# OLDbattery_board.net
KiCad netlist of a schematic drawn in EAGLE
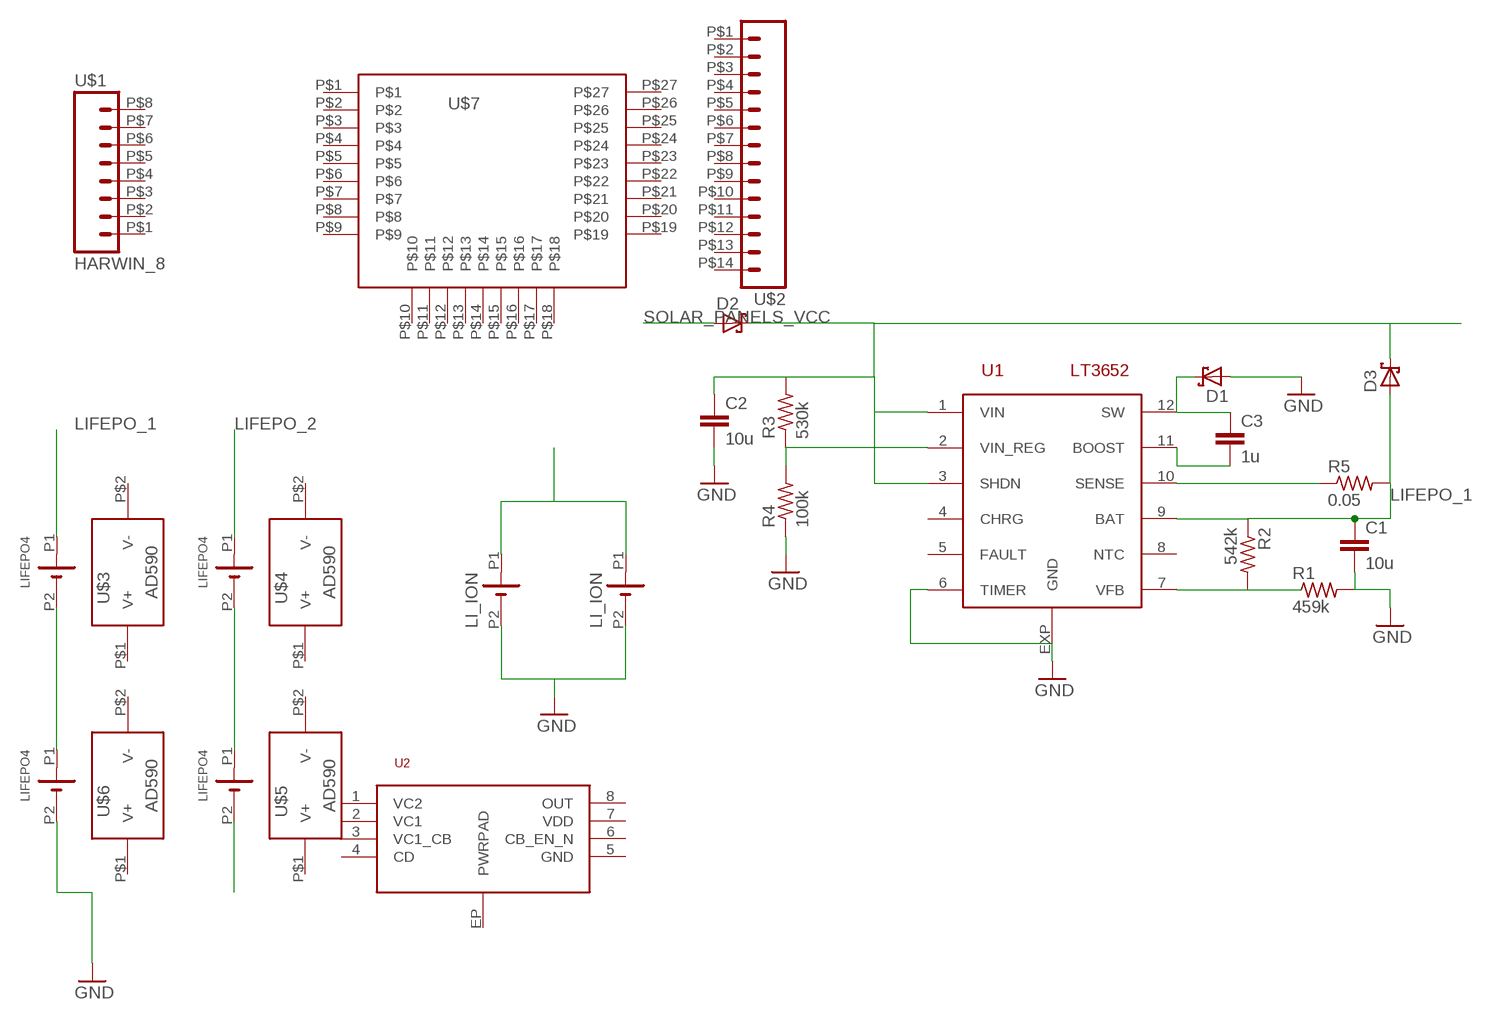
[diagram p0: schematic, sheet 1]

(export (version "E")
  (design (tool "Eeschema 10.0.6"))
  (components
    (comp (ref "C1")
      (value "10u")
      (footprint "eagle-import:C1210")
      (libsource (lib "eagle-import") (part "C-EUC1210"))
    )
    (comp (ref "C2")
      (value "10u")
      (footprint "eagle-import:C1210")
      (libsource (lib "eagle-import") (part "C-EUC1210"))
    )
    (comp (ref "C3")
      (value "1u")
      (footprint "eagle-import:C0805")
      (libsource (lib "eagle-import") (part "C-EUC0805"))
    )
    (comp (ref "D1")
      (value "SCHOTTKY-DIODE")
      (footprint "eagle-import:SOD123")
      (libsource (lib "eagle-import") (part "SCHOTTKY-DIODE"))
    )
    (comp (ref "D2")
      (value "SCHOTTKY-DIODE")
      (footprint "eagle-import:SOD123")
      (libsource (lib "eagle-import") (part "SCHOTTKY-DIODE"))
    )
    (comp (ref "D3")
      (value "SCHOTTKY-DIODE")
      (footprint "eagle-import:SOD123")
      (libsource (lib "eagle-import") (part "SCHOTTKY-DIODE"))
    )
    (comp (ref "LFP1")
      (value "LIFEPO4")
      (footprint "eagle-import:LIFEPO4")
      (libsource (lib "eagle-import") (part "LIFEPO4"))
    )
    (comp (ref "LFP2")
      (value "LIFEPO4")
      (footprint "eagle-import:LIFEPO4")
      (libsource (lib "eagle-import") (part "LIFEPO4"))
    )
    (comp (ref "LFP3")
      (value "LIFEPO4")
      (footprint "eagle-import:LIFEPO4")
      (libsource (lib "eagle-import") (part "LIFEPO4"))
    )
    (comp (ref "LFP4")
      (value "LIFEPO4")
      (footprint "eagle-import:LIFEPO4")
      (libsource (lib "eagle-import") (part "LIFEPO4"))
    )
    (comp (ref "R1")
      (value "459k")
      (footprint "eagle-import:R0805")
      (libsource (lib "eagle-import") (part "R-US_R0805"))
    )
    (comp (ref "R2")
      (value "542k")
      (footprint "eagle-import:R0805")
      (libsource (lib "eagle-import") (part "R-US_R0805"))
    )
    (comp (ref "R3")
      (value "530k")
      (footprint "eagle-import:R0805")
      (libsource (lib "eagle-import") (part "R-US_R0805"))
    )
    (comp (ref "R4")
      (value "100k")
      (footprint "eagle-import:R0805")
      (libsource (lib "eagle-import") (part "R-US_R0805"))
    )
    (comp (ref "R5")
      (value "0.05")
      (footprint "eagle-import:R0805")
      (libsource (lib "eagle-import") (part "R-US_R0805"))
    )
    (comp (ref "U$1")
      (value "HARWIN_8")
      (footprint "eagle-import:HARWIN_8")
      (libsource (lib "eagle-import") (part "HARWIN_8"))
    )
    (comp (ref "U$2")
      (value "HARWIN_14")
      (footprint "eagle-import:HARWIN_DATAMATE_14")
      (libsource (lib "eagle-import") (part "HARWIN_14"))
    )
    (comp (ref "U$3")
      (value "AD590-TH")
      (footprint "eagle-import:AD590TH")
      (libsource (lib "eagle-import") (part "AD590-TH"))
    )
    (comp (ref "U$4")
      (value "AD590-TH")
      (footprint "eagle-import:AD590TH")
      (libsource (lib "eagle-import") (part "AD590-TH"))
    )
    (comp (ref "U$5")
      (value "AD590-TH")
      (footprint "eagle-import:AD590TH")
      (libsource (lib "eagle-import") (part "AD590-TH"))
    )
    (comp (ref "U$6")
      (value "AD590-TH")
      (footprint "eagle-import:AD590TH")
      (libsource (lib "eagle-import") (part "AD590-TH"))
    )
    (comp (ref "U$7")
      (value "HARWIN_27")
      (footprint "eagle-import:HARWIN_DATAMATE_27")
      (libsource (lib "eagle-import") (part "HARWIN_27"))
    )
    (comp (ref "U$8")
      (value "LI_ION")
      (footprint "eagle-import:LI_ION")
      (libsource (lib "eagle-import") (part "LI_ION"))
    )
    (comp (ref "U$9")
      (value "LI_ION")
      (footprint "eagle-import:LI_ION")
      (libsource (lib "eagle-import") (part "LI_ION"))
    )
    (comp (ref "U1")
      (value "LT3652")
      (footprint "eagle-import:MSOP12")
      (libsource (lib "eagle-import") (part "LT3652"))
    )
    (comp (ref "U2")
      (value "BQ29209")
      (footprint "eagle-import:VSON8")
      (libsource (lib "eagle-import") (part "BQ29209"))
    )
  )
  (nets
    (net (code "1") (name "/LIFEPO_1") (class "Default")
      (node (ref "C1") (pin "1") (pinfunction "1_1") (pintype "passive"))
      (node (ref "D3") (pin "A") (pinfunction "A_A") (pintype "passive"))
      (node (ref "LFP1") (pin "P1") (pinfunction "+_P1") (pintype "passive"))
      (node (ref "R2") (pin "1") (pinfunction "1_1") (pintype "passive"))
      (node (ref "R5") (pin "2") (pinfunction "2_2") (pintype "passive"))
      (node (ref "U1") (pin "9") (pinfunction "BAT_9") (pintype "bidirectional"))
    )
    (net (code "2") (name "/LIFEPO_2") (class "Default")
      (node (ref "LFP2") (pin "P1") (pinfunction "+_P1") (pintype "passive"))
    )
    (net (code "3") (name "/SOLAR_PANELS_VCC") (class "Default")
      (node (ref "D2") (pin "A") (pinfunction "A_A") (pintype "passive"))
    )
    (net (code "4") (name "GND") (class "Default")
      (node (ref "C1") (pin "2") (pinfunction "2_2") (pintype "passive"))
      (node (ref "C2") (pin "2") (pinfunction "2_2") (pintype "passive"))
      (node (ref "D1") (pin "A") (pinfunction "A_A") (pintype "passive"))
      (node (ref "LFP3") (pin "P2") (pinfunction "-_P2") (pintype "passive"))
      (node (ref "R1") (pin "2") (pinfunction "2_2") (pintype "passive"))
      (node (ref "R4") (pin "1") (pinfunction "1_1") (pintype "passive"))
      (node (ref "U$8") (pin "P2") (pinfunction "-_P2") (pintype "passive"))
      (node (ref "U$9") (pin "P2") (pinfunction "-_P2") (pintype "passive"))
      (node (ref "U1") (pin "6") (pinfunction "TIMER_6") (pintype "bidirectional"))
      (node (ref "U1") (pin "EXP") (pinfunction "GND_EXP") (pintype "bidirectional"))
    )
    (net (code "5") (name "Net-(LFP1--)") (class "Default")
      (node (ref "LFP1") (pin "P2") (pinfunction "-_P2") (pintype "passive"))
      (node (ref "LFP3") (pin "P1") (pinfunction "+_P1") (pintype "passive"))
    )
    (net (code "6") (name "Net-(LFP2--)") (class "Default")
      (node (ref "LFP2") (pin "P2") (pinfunction "-_P2") (pintype "passive"))
      (node (ref "LFP4") (pin "P1") (pinfunction "+_P1") (pintype "passive"))
    )
    (net (code "7") (name "Net-(U$8-+)") (class "Default")
      (node (ref "U$8") (pin "P1") (pinfunction "+_P1") (pintype "passive"))
      (node (ref "U$9") (pin "P1") (pinfunction "+_P1") (pintype "passive"))
    )
    (net (code "8") (name "Net-(U1-BOOST)") (class "Default")
      (node (ref "C3") (pin "2") (pinfunction "2_2") (pintype "passive"))
      (node (ref "U1") (pin "11") (pinfunction "BOOST_11") (pintype "bidirectional"))
    )
    (net (code "9") (name "Net-(U1-SENSE)") (class "Default")
      (node (ref "R5") (pin "1") (pinfunction "1_1") (pintype "passive"))
      (node (ref "U1") (pin "10") (pinfunction "SENSE_10") (pintype "bidirectional"))
    )
    (net (code "10") (name "Net-(U1-SHDN)") (class "Default")
      (node (ref "C2") (pin "1") (pinfunction "1_1") (pintype "passive"))
      (node (ref "D2") (pin "C") (pinfunction "C_C") (pintype "passive"))
      (node (ref "D3") (pin "C") (pinfunction "C_C") (pintype "passive"))
      (node (ref "R3") (pin "2") (pinfunction "2_2") (pintype "passive"))
      (node (ref "U1") (pin "1") (pinfunction "VIN_1") (pintype "bidirectional"))
      (node (ref "U1") (pin "3") (pinfunction "SHDN_3") (pintype "bidirectional"))
    )
    (net (code "11") (name "Net-(U1-SW)") (class "Default")
      (node (ref "C3") (pin "1") (pinfunction "1_1") (pintype "passive"))
      (node (ref "D1") (pin "C") (pinfunction "C_C") (pintype "passive"))
      (node (ref "U1") (pin "12") (pinfunction "SW_12") (pintype "bidirectional"))
    )
    (net (code "12") (name "Net-(U1-VFB)") (class "Default")
      (node (ref "R2") (pin "2") (pinfunction "2_2") (pintype "passive"))
      (node (ref "U1") (pin "7") (pinfunction "VFB_7") (pintype "bidirectional"))
    )
    (net (code "13") (name "Net-(U1-VIN_REG)") (class "Default")
      (node (ref "R3") (pin "1") (pinfunction "1_1") (pintype "passive"))
      (node (ref "R4") (pin "2") (pinfunction "2_2") (pintype "passive"))
      (node (ref "U1") (pin "2") (pinfunction "VIN_REG_2") (pintype "bidirectional"))
    )
    (net (code "14") (name "unconnected-(LFP4---PadP2)") (class "Default")
      (node (ref "LFP4") (pin "P2") (pinfunction "-_P2") (pintype "passive"))
    )
    (net (code "15") (name "unconnected-(R1-Pad1)") (class "Default")
      (node (ref "R1") (pin "1") (pinfunction "1_1") (pintype "passive"))
    )
    (net (code "16") (name "unconnected-(U$1-1-PadP$1)") (class "Default")
      (node (ref "U$1") (pin "P$1") (pinfunction "1_P$1") (pintype "passive"))
    )
    (net (code "17") (name "unconnected-(U$1-2-PadP$2)") (class "Default")
      (node (ref "U$1") (pin "P$2") (pinfunction "2_P$2") (pintype "passive"))
    )
    (net (code "18") (name "unconnected-(U$1-3-PadP$3)") (class "Default")
      (node (ref "U$1") (pin "P$3") (pinfunction "3_P$3") (pintype "passive"))
    )
    (net (code "19") (name "unconnected-(U$1-4-PadP$4)") (class "Default")
      (node (ref "U$1") (pin "P$4") (pinfunction "4_P$4") (pintype "passive"))
    )
    (net (code "20") (name "unconnected-(U$1-5-PadP$5)") (class "Default")
      (node (ref "U$1") (pin "P$5") (pinfunction "5_P$5") (pintype "passive"))
    )
    (net (code "21") (name "unconnected-(U$1-6-PadP$6)") (class "Default")
      (node (ref "U$1") (pin "P$6") (pinfunction "6_P$6") (pintype "passive"))
    )
    (net (code "22") (name "unconnected-(U$1-7-PadP$7)") (class "Default")
      (node (ref "U$1") (pin "P$7") (pinfunction "7_P$7") (pintype "passive"))
    )
    (net (code "23") (name "unconnected-(U$1-8-PadP$8)") (class "Default")
      (node (ref "U$1") (pin "P$8") (pinfunction "8_P$8") (pintype "passive"))
    )
    (net (code "24") (name "unconnected-(U$2-1-PadP$1)") (class "Default")
      (node (ref "U$2") (pin "P$1") (pinfunction "1_P$1") (pintype "passive"))
    )
    (net (code "25") (name "unconnected-(U$2-2-PadP$2)") (class "Default")
      (node (ref "U$2") (pin "P$2") (pinfunction "2_P$2") (pintype "passive"))
    )
    (net (code "26") (name "unconnected-(U$2-3-PadP$3)") (class "Default")
      (node (ref "U$2") (pin "P$3") (pinfunction "3_P$3") (pintype "passive"))
    )
    (net (code "27") (name "unconnected-(U$2-4-PadP$4)") (class "Default")
      (node (ref "U$2") (pin "P$4") (pinfunction "4_P$4") (pintype "passive"))
    )
    (net (code "28") (name "unconnected-(U$2-5-PadP$5)") (class "Default")
      (node (ref "U$2") (pin "P$5") (pinfunction "5_P$5") (pintype "passive"))
    )
    (net (code "29") (name "unconnected-(U$2-6-PadP$6)") (class "Default")
      (node (ref "U$2") (pin "P$6") (pinfunction "6_P$6") (pintype "passive"))
    )
    (net (code "30") (name "unconnected-(U$2-7-PadP$7)") (class "Default")
      (node (ref "U$2") (pin "P$7") (pinfunction "7_P$7") (pintype "passive"))
    )
    (net (code "31") (name "unconnected-(U$2-8-PadP$8)") (class "Default")
      (node (ref "U$2") (pin "P$8") (pinfunction "8_P$8") (pintype "passive"))
    )
    (net (code "32") (name "unconnected-(U$2-9-PadP$9)") (class "Default")
      (node (ref "U$2") (pin "P$9") (pinfunction "9_P$9") (pintype "passive"))
    )
    (net (code "33") (name "unconnected-(U$2-10-PadP$10)") (class "Default")
      (node (ref "U$2") (pin "P$10") (pinfunction "10_P$10") (pintype "passive"))
    )
    (net (code "34") (name "unconnected-(U$2-11-PadP$11)") (class "Default")
      (node (ref "U$2") (pin "P$11") (pinfunction "11_P$11") (pintype "passive"))
    )
    (net (code "35") (name "unconnected-(U$2-12-PadP$12)") (class "Default")
      (node (ref "U$2") (pin "P$12") (pinfunction "12_P$12") (pintype "passive"))
    )
    (net (code "36") (name "unconnected-(U$2-13-PadP$13)") (class "Default")
      (node (ref "U$2") (pin "P$13") (pinfunction "13_P$13") (pintype "passive"))
    )
    (net (code "37") (name "unconnected-(U$2-14-PadP$14)") (class "Default")
      (node (ref "U$2") (pin "P$14") (pinfunction "14_P$14") (pintype "passive"))
    )
    (net (code "38") (name "unconnected-(U$3-V+-PadP$1)") (class "Default")
      (node (ref "U$3") (pin "P$1") (pinfunction "V+_P$1") (pintype "bidirectional"))
    )
    (net (code "39") (name "unconnected-(U$3-V--PadP$2)") (class "Default")
      (node (ref "U$3") (pin "P$2") (pinfunction "V-_P$2") (pintype "bidirectional"))
    )
    (net (code "40") (name "unconnected-(U$4-V+-PadP$1)") (class "Default")
      (node (ref "U$4") (pin "P$1") (pinfunction "V+_P$1") (pintype "bidirectional"))
    )
    (net (code "41") (name "unconnected-(U$4-V--PadP$2)") (class "Default")
      (node (ref "U$4") (pin "P$2") (pinfunction "V-_P$2") (pintype "bidirectional"))
    )
    (net (code "42") (name "unconnected-(U$5-V+-PadP$1)") (class "Default")
      (node (ref "U$5") (pin "P$1") (pinfunction "V+_P$1") (pintype "bidirectional"))
    )
    (net (code "43") (name "unconnected-(U$5-V--PadP$2)") (class "Default")
      (node (ref "U$5") (pin "P$2") (pinfunction "V-_P$2") (pintype "bidirectional"))
    )
    (net (code "44") (name "unconnected-(U$6-V+-PadP$1)") (class "Default")
      (node (ref "U$6") (pin "P$1") (pinfunction "V+_P$1") (pintype "bidirectional"))
    )
    (net (code "45") (name "unconnected-(U$6-V--PadP$2)") (class "Default")
      (node (ref "U$6") (pin "P$2") (pinfunction "V-_P$2") (pintype "bidirectional"))
    )
    (net (code "46") (name "unconnected-(U$7-PadP$1)") (class "Default")
      (node (ref "U$7") (pin "P$1") (pinfunction "P$1_P$1") (pintype "bidirectional"))
    )
    (net (code "47") (name "unconnected-(U$7-PadP$2)") (class "Default")
      (node (ref "U$7") (pin "P$2") (pinfunction "P$2_P$2") (pintype "bidirectional"))
    )
    (net (code "48") (name "unconnected-(U$7-PadP$3)") (class "Default")
      (node (ref "U$7") (pin "P$3") (pinfunction "P$3_P$3") (pintype "bidirectional"))
    )
    (net (code "49") (name "unconnected-(U$7-PadP$4)") (class "Default")
      (node (ref "U$7") (pin "P$4") (pinfunction "P$4_P$4") (pintype "bidirectional"))
    )
    (net (code "50") (name "unconnected-(U$7-PadP$5)") (class "Default")
      (node (ref "U$7") (pin "P$5") (pinfunction "P$5_P$5") (pintype "bidirectional"))
    )
    (net (code "51") (name "unconnected-(U$7-PadP$6)") (class "Default")
      (node (ref "U$7") (pin "P$6") (pinfunction "P$6_P$6") (pintype "bidirectional"))
    )
    (net (code "52") (name "unconnected-(U$7-PadP$7)") (class "Default")
      (node (ref "U$7") (pin "P$7") (pinfunction "P$7_P$7") (pintype "bidirectional"))
    )
    (net (code "53") (name "unconnected-(U$7-PadP$8)") (class "Default")
      (node (ref "U$7") (pin "P$8") (pinfunction "P$8_P$8") (pintype "bidirectional"))
    )
    (net (code "54") (name "unconnected-(U$7-PadP$9)") (class "Default")
      (node (ref "U$7") (pin "P$9") (pinfunction "P$9_P$9") (pintype "bidirectional"))
    )
    (net (code "55") (name "unconnected-(U$7-PadP$10)") (class "Default")
      (node (ref "U$7") (pin "P$10") (pinfunction "P$10_P$10") (pintype "bidirectional"))
    )
    (net (code "56") (name "unconnected-(U$7-PadP$11)") (class "Default")
      (node (ref "U$7") (pin "P$11") (pinfunction "P$11_P$11") (pintype "bidirectional"))
    )
    (net (code "57") (name "unconnected-(U$7-PadP$12)") (class "Default")
      (node (ref "U$7") (pin "P$12") (pinfunction "P$12_P$12") (pintype "bidirectional"))
    )
    (net (code "58") (name "unconnected-(U$7-PadP$13)") (class "Default")
      (node (ref "U$7") (pin "P$13") (pinfunction "P$13_P$13") (pintype "bidirectional"))
    )
    (net (code "59") (name "unconnected-(U$7-PadP$14)") (class "Default")
      (node (ref "U$7") (pin "P$14") (pinfunction "P$14_P$14") (pintype "bidirectional"))
    )
    (net (code "60") (name "unconnected-(U$7-PadP$15)") (class "Default")
      (node (ref "U$7") (pin "P$15") (pinfunction "P$15_P$15") (pintype "bidirectional"))
    )
    (net (code "61") (name "unconnected-(U$7-PadP$16)") (class "Default")
      (node (ref "U$7") (pin "P$16") (pinfunction "P$16_P$16") (pintype "bidirectional"))
    )
    (net (code "62") (name "unconnected-(U$7-PadP$17)") (class "Default")
      (node (ref "U$7") (pin "P$17") (pinfunction "P$17_P$17") (pintype "bidirectional"))
    )
    (net (code "63") (name "unconnected-(U$7-PadP$18)") (class "Default")
      (node (ref "U$7") (pin "P$18") (pinfunction "P$18_P$18") (pintype "bidirectional"))
    )
    (net (code "64") (name "unconnected-(U$7-PadP$19)") (class "Default")
      (node (ref "U$7") (pin "P$19") (pinfunction "P$19_P$19") (pintype "bidirectional"))
    )
    (net (code "65") (name "unconnected-(U$7-PadP$20)") (class "Default")
      (node (ref "U$7") (pin "P$20") (pinfunction "P$20_P$20") (pintype "bidirectional"))
    )
    (net (code "66") (name "unconnected-(U$7-PadP$21)") (class "Default")
      (node (ref "U$7") (pin "P$21") (pinfunction "P$21_P$21") (pintype "bidirectional"))
    )
    (net (code "67") (name "unconnected-(U$7-PadP$22)") (class "Default")
      (node (ref "U$7") (pin "P$22") (pinfunction "P$22_P$22") (pintype "bidirectional"))
    )
    (net (code "68") (name "unconnected-(U$7-PadP$23)") (class "Default")
      (node (ref "U$7") (pin "P$23") (pinfunction "P$23_P$23") (pintype "bidirectional"))
    )
    (net (code "69") (name "unconnected-(U$7-PadP$24)") (class "Default")
      (node (ref "U$7") (pin "P$24") (pinfunction "P$24_P$24") (pintype "bidirectional"))
    )
    (net (code "70") (name "unconnected-(U$7-PadP$25)") (class "Default")
      (node (ref "U$7") (pin "P$25") (pinfunction "P$25_P$25") (pintype "bidirectional"))
    )
    (net (code "71") (name "unconnected-(U$7-PadP$26)") (class "Default")
      (node (ref "U$7") (pin "P$26") (pinfunction "P$26_P$26") (pintype "bidirectional"))
    )
    (net (code "72") (name "unconnected-(U$7-PadP$27)") (class "Default")
      (node (ref "U$7") (pin "P$27") (pinfunction "P$27_P$27") (pintype "bidirectional"))
    )
    (net (code "73") (name "unconnected-(U1-CHRG-Pad4)") (class "Default")
      (node (ref "U1") (pin "4") (pinfunction "CHRG_4") (pintype "bidirectional"))
    )
    (net (code "74") (name "unconnected-(U1-FAULT-Pad5)") (class "Default")
      (node (ref "U1") (pin "5") (pinfunction "FAULT_5") (pintype "bidirectional"))
    )
    (net (code "75") (name "unconnected-(U1-NTC-Pad8)") (class "Default")
      (node (ref "U1") (pin "8") (pinfunction "NTC_8") (pintype "bidirectional"))
    )
    (net (code "76") (name "unconnected-(U2-CB_EN_N-Pad6)") (class "Default")
      (node (ref "U2") (pin "6") (pinfunction "CB_EN_N_6") (pintype "bidirectional"))
    )
    (net (code "77") (name "unconnected-(U2-CD-Pad4)") (class "Default")
      (node (ref "U2") (pin "4") (pinfunction "CD_4") (pintype "bidirectional"))
    )
    (net (code "78") (name "unconnected-(U2-GND-Pad5)") (class "Default")
      (node (ref "U2") (pin "5") (pinfunction "GND_5") (pintype "bidirectional"))
    )
    (net (code "79") (name "unconnected-(U2-OUT-Pad8)") (class "Default")
      (node (ref "U2") (pin "8") (pinfunction "OUT_8") (pintype "bidirectional"))
    )
    (net (code "80") (name "unconnected-(U2-PWRPAD-PadEP)") (class "Default")
      (node (ref "U2") (pin "EP") (pinfunction "PWRPAD_EP") (pintype "bidirectional"))
    )
    (net (code "81") (name "unconnected-(U2-VC1-Pad2)") (class "Default")
      (node (ref "U2") (pin "2") (pinfunction "VC1_2") (pintype "bidirectional"))
    )
    (net (code "82") (name "unconnected-(U2-VC1_CB-Pad3)") (class "Default")
      (node (ref "U2") (pin "3") (pinfunction "VC1_CB_3") (pintype "bidirectional"))
    )
    (net (code "83") (name "unconnected-(U2-VC2-Pad1)") (class "Default")
      (node (ref "U2") (pin "1") (pinfunction "VC2_1") (pintype "bidirectional"))
    )
    (net (code "84") (name "unconnected-(U2-VDD-Pad7)") (class "Default")
      (node (ref "U2") (pin "7") (pinfunction "VDD_7") (pintype "bidirectional"))
    )
  )
)
